# v2.net
KiCad netlist of a schematic drawn in EAGLE
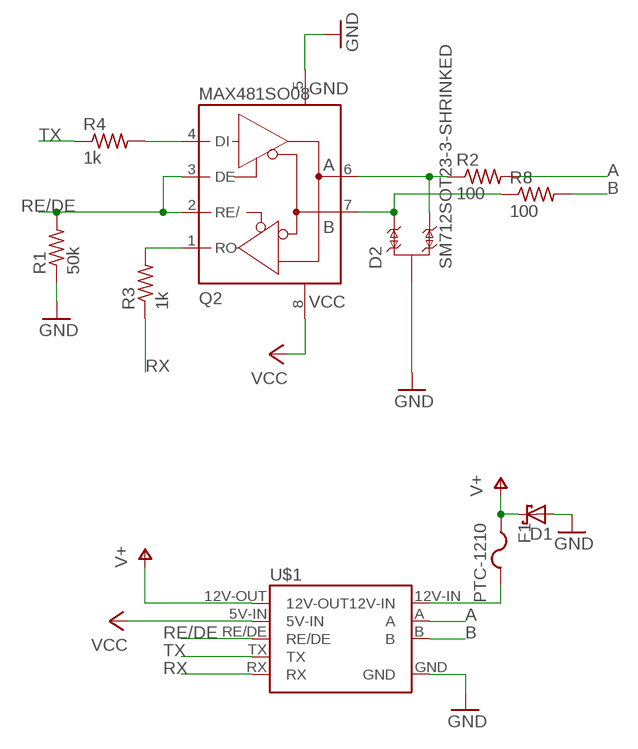
[diagram p0: schematic, sheet 1]

(export (version "E")
  (design (tool "Eeschema 10.0.6"))
  (components
    (comp (ref "D1")
      (value "SCHOTTKY-DIODESMC")
      (footprint "eagle-import:SMC")
      (libsource (lib "eagle-import") (part "SCHOTTKY-DIODESMC"))
    )
    (comp (ref "D2")
      (value "SM712SOT23-3-SHRINKED")
      (footprint "eagle-import:SOT23-3-SHRINKED")
      (libsource (lib "eagle-import") (part "SM712SOT23-3-SHRINKED"))
    )
    (comp (ref "F1")
      (value "PTC-1210")
      (footprint "eagle-import:1210")
      (libsource (lib "eagle-import") (part "PTC-1210"))
    )
    (comp (ref "Q2")
      (value "MAX481SO08")
      (footprint "eagle-import:SO08")
      (libsource (lib "eagle-import") (part "MAX481SO08"))
    )
    (comp (ref "R1")
      (value "50k")
      (footprint "eagle-import:R0603")
      (libsource (lib "eagle-import") (part "R-US_R0603"))
    )
    (comp (ref "R2")
      (value "100")
      (footprint "eagle-import:R0603")
      (libsource (lib "eagle-import") (part "R-US_R0603"))
    )
    (comp (ref "R3")
      (value "1k")
      (footprint "eagle-import:R0603")
      (libsource (lib "eagle-import") (part "R-US_R0603"))
    )
    (comp (ref "R4")
      (value "1k")
      (footprint "eagle-import:R0603")
      (libsource (lib "eagle-import") (part "R-US_R0603"))
    )
    (comp (ref "R8")
      (value "100")
      (footprint "eagle-import:R0603")
      (libsource (lib "eagle-import") (part "R-US_R0603"))
    )
    (comp (ref "U$1")
      (value "RS485-ADAPTER")
      (footprint "eagle-import:RS485-ADAPTOR")
      (libsource (lib "eagle-import") (part "RS485-ADAPTER"))
    )
  )
  (nets
    (net (code "1") (name "/A") (class "Default")
      (node (ref "R2") (pin "2") (pinfunction "2_2") (pintype "passive"))
      (node (ref "U$1") (pin "A") (pinfunction "A_A") (pintype "bidirectional"))
    )
    (net (code "2") (name "/B") (class "Default")
      (node (ref "R8") (pin "2") (pinfunction "2_2") (pintype "passive"))
      (node (ref "U$1") (pin "B") (pinfunction "B_B") (pintype "bidirectional"))
    )
    (net (code "3") (name "/RE{slash}DE") (class "Default")
      (node (ref "Q2") (pin "2") (pinfunction "RE/_2") (pintype "input"))
      (node (ref "Q2") (pin "3") (pinfunction "DE_3") (pintype "input"))
      (node (ref "R1") (pin "2") (pinfunction "2_2") (pintype "passive"))
      (node (ref "U$1") (pin "RE/DE") (pinfunction "RE/DE_RE/DE") (pintype "bidirectional"))
    )
    (net (code "4") (name "/RX") (class "Default")
      (node (ref "R3") (pin "1") (pinfunction "1_1") (pintype "passive"))
      (node (ref "U$1") (pin "RX") (pinfunction "RX_RX") (pintype "bidirectional"))
    )
    (net (code "5") (name "/TX") (class "Default")
      (node (ref "R4") (pin "1") (pinfunction "1_1") (pintype "passive"))
      (node (ref "U$1") (pin "TX") (pinfunction "TX_TX") (pintype "bidirectional"))
    )
    (net (code "6") (name "GND") (class "Default")
      (node (ref "D1") (pin "A") (pinfunction "A_A") (pintype "passive"))
      (node (ref "D2") (pin "3") (pinfunction "3_3") (pintype "passive"))
      (node (ref "Q2") (pin "5") (pinfunction "GND_5") (pintype "power_in"))
      (node (ref "R1") (pin "1") (pinfunction "1_1") (pintype "passive"))
      (node (ref "U$1") (pin "GND") (pinfunction "GND_GND") (pintype "power_in"))
    )
    (net (code "7") (name "Net-(F1-Pad2)") (class "Default")
      (node (ref "F1") (pin "2") (pinfunction "2_2") (pintype "passive"))
      (node (ref "U$1") (pin "12V-IN") (pinfunction "12V-IN_12V-IN") (pintype "power_in"))
    )
    (net (code "8") (name "Net-(Q2-A)") (class "Default")
      (node (ref "D2") (pin "1") (pinfunction "1_1") (pintype "passive"))
      (node (ref "Q2") (pin "6") (pinfunction "A_6") (pintype "passive"))
      (node (ref "R2") (pin "1") (pinfunction "1_1") (pintype "passive"))
    )
    (net (code "9") (name "Net-(Q2-B)") (class "Default")
      (node (ref "D2") (pin "2") (pinfunction "2_2") (pintype "passive"))
      (node (ref "Q2") (pin "7") (pinfunction "B_7") (pintype "passive"))
      (node (ref "R8") (pin "1") (pinfunction "1_1") (pintype "passive"))
    )
    (net (code "10") (name "Net-(Q2-DI)") (class "Default")
      (node (ref "Q2") (pin "4") (pinfunction "DI_4") (pintype "input"))
      (node (ref "R4") (pin "2") (pinfunction "2_2") (pintype "passive"))
    )
    (net (code "11") (name "Net-(Q2-RO)") (class "Default")
      (node (ref "Q2") (pin "1") (pinfunction "RO_1") (pintype "output"))
      (node (ref "R3") (pin "2") (pinfunction "2_2") (pintype "passive"))
    )
    (net (code "12") (name "V+") (class "Default")
      (node (ref "D1") (pin "C") (pinfunction "C_C") (pintype "passive"))
      (node (ref "F1") (pin "1") (pinfunction "1_1") (pintype "passive"))
      (node (ref "U$1") (pin "12V-OUT") (pinfunction "12V-OUT_12V-OUT") (pintype "power_in"))
    )
    (net (code "13") (name "VCC") (class "Default")
      (node (ref "Q2") (pin "8") (pinfunction "+5V_8") (pintype "power_in"))
      (node (ref "U$1") (pin "5V-IN") (pinfunction "5V-IN_5V-IN") (pintype "power_in"))
    )
  )
)
